# Segnalino.net
KiCad netlist of a schematic drawn in EAGLE
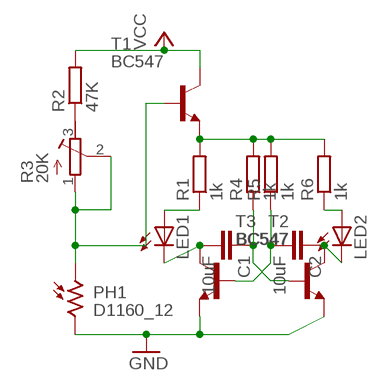
[diagram p0: schematic, sheet 1]

(export (version "E")
  (design (tool "Eeschema 10.0.6"))
  (components
    (comp (ref "C1")
      (value "10uF")
      (footprint "eagle-import:C025-024X044")
      (libsource (lib "eagle-import") (part "C-EU025-024X044"))
    )
    (comp (ref "C2")
      (value "10uF")
      (footprint "eagle-import:C025-024X044")
      (libsource (lib "eagle-import") (part "C-EU025-024X044"))
    )
    (comp (ref "LED1")
      (value "LED3MM")
      (footprint "eagle-import:LED3MM")
      (libsource (lib "eagle-import") (part "LED3MM"))
    )
    (comp (ref "LED2")
      (value "LED3MM")
      (footprint "eagle-import:LED3MM")
      (libsource (lib "eagle-import") (part "LED3MM"))
    )
    (comp (ref "PH1")
      (value "D1160_12")
      (footprint "eagle-import:D11XX")
      (libsource (lib "eagle-import") (part "D1160_12"))
    )
    (comp (ref "R1")
      (value "1k")
      (footprint "eagle-import:0204V")
      (libsource (lib "eagle-import") (part "R-EU_0204/2V"))
    )
    (comp (ref "R2")
      (value "47K")
      (footprint "eagle-import:0204V")
      (libsource (lib "eagle-import") (part "R-EU_0204/2V"))
    )
    (comp (ref "R3")
      (value "20K")
      (footprint "eagle-import:RTRIM3339P")
      (libsource (lib "eagle-import") (part "R-TRIMM3339P"))
    )
    (comp (ref "R4")
      (value "1k")
      (footprint "eagle-import:0204V")
      (libsource (lib "eagle-import") (part "R-EU_0204/2V"))
    )
    (comp (ref "R5")
      (value "1k")
      (footprint "eagle-import:0204V")
      (libsource (lib "eagle-import") (part "R-EU_0204/2V"))
    )
    (comp (ref "R6")
      (value "1k")
      (footprint "eagle-import:0204V")
      (libsource (lib "eagle-import") (part "R-EU_0204/2V"))
    )
    (comp (ref "T1")
      (value "BC547")
      (footprint "eagle-import:TO92")
      (libsource (lib "eagle-import") (part "BC547"))
    )
    (comp (ref "T2")
      (value "BC547")
      (footprint "eagle-import:TO92")
      (libsource (lib "eagle-import") (part "BC547"))
    )
    (comp (ref "T3")
      (value "BC547")
      (footprint "eagle-import:TO92")
      (libsource (lib "eagle-import") (part "BC547"))
    )
  )
  (nets
    (net (code "1") (name "GND") (class "Default")
      (node (ref "PH1") (pin "2") (pinfunction "2_2") (pintype "passive"))
      (node (ref "T2") (pin "1") (pinfunction "E_1") (pintype "passive"))
      (node (ref "T3") (pin "1") (pinfunction "E_1") (pintype "passive"))
    )
    (net (code "2") (name "Net-(LED1-C)") (class "Default")
      (node (ref "C1") (pin "2") (pinfunction "2_2") (pintype "passive"))
      (node (ref "LED1") (pin "K") (pinfunction "C_K") (pintype "passive"))
      (node (ref "T2") (pin "3") (pinfunction "C_3") (pintype "passive"))
    )
    (net (code "3") (name "Net-(LED1-PadA)") (class "Default")
      (node (ref "LED1") (pin "A") (pinfunction "A_A") (pintype "passive"))
      (node (ref "R1") (pin "1") (pinfunction "1_1") (pintype "passive"))
    )
    (net (code "4") (name "Net-(LED2-C)") (class "Default")
      (node (ref "C2") (pin "1") (pinfunction "1_1") (pintype "passive"))
      (node (ref "LED2") (pin "K") (pinfunction "C_K") (pintype "passive"))
      (node (ref "T3") (pin "3") (pinfunction "C_3") (pintype "passive"))
    )
    (net (code "5") (name "Net-(LED2-PadA)") (class "Default")
      (node (ref "LED2") (pin "A") (pinfunction "A_A") (pintype "passive"))
      (node (ref "R6") (pin "1") (pinfunction "1_1") (pintype "passive"))
    )
    (net (code "6") (name "Net-(R3-A)") (class "Default")
      (node (ref "PH1") (pin "1") (pinfunction "1_1") (pintype "passive"))
      (node (ref "R3") (pin "1") (pinfunction "A_1") (pintype "passive"))
      (node (ref "R3") (pin "2") (pinfunction "S_2") (pintype "passive"))
      (node (ref "T1") (pin "2") (pinfunction "B_2") (pintype "passive"))
    )
    (net (code "7") (name "Net-(R3-E)") (class "Default")
      (node (ref "R2") (pin "1") (pinfunction "1_1") (pintype "passive"))
      (node (ref "R3") (pin "3") (pinfunction "E_3") (pintype "passive"))
    )
    (net (code "8") (name "Net-(T1-E)") (class "Default")
      (node (ref "R1") (pin "2") (pinfunction "2_2") (pintype "passive"))
      (node (ref "R4") (pin "2") (pinfunction "2_2") (pintype "passive"))
      (node (ref "R5") (pin "2") (pinfunction "2_2") (pintype "passive"))
      (node (ref "R6") (pin "2") (pinfunction "2_2") (pintype "passive"))
      (node (ref "T1") (pin "1") (pinfunction "E_1") (pintype "passive"))
    )
    (net (code "9") (name "Net-(T2-B)") (class "Default")
      (node (ref "C2") (pin "2") (pinfunction "2_2") (pintype "passive"))
      (node (ref "R5") (pin "1") (pinfunction "1_1") (pintype "passive"))
      (node (ref "T2") (pin "2") (pinfunction "B_2") (pintype "passive"))
    )
    (net (code "10") (name "Net-(T3-B)") (class "Default")
      (node (ref "C1") (pin "1") (pinfunction "1_1") (pintype "passive"))
      (node (ref "R4") (pin "1") (pinfunction "1_1") (pintype "passive"))
      (node (ref "T3") (pin "2") (pinfunction "B_2") (pintype "passive"))
    )
    (net (code "11") (name "VCC") (class "Default")
      (node (ref "R2") (pin "2") (pinfunction "2_2") (pintype "passive"))
      (node (ref "T1") (pin "3") (pinfunction "C_3") (pintype "passive"))
    )
  )
)
